# DUT1.net
KiCad netlist of a schematic drawn in Altium Designer
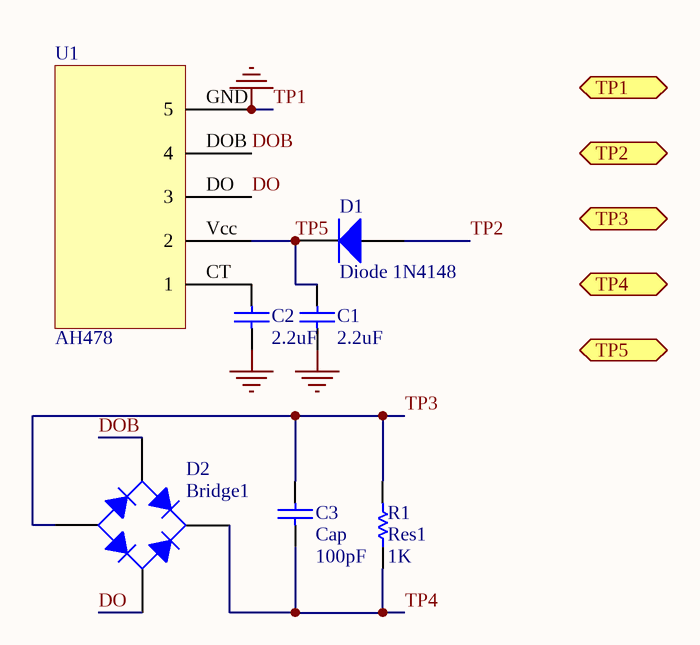
[diagram p0: DUT1.SchDoc]

(export (version "E")
  (design (tool "Eeschema 10.0.6"))
  (components
    (comp (ref "C1")
      (value "2.2uF")
      (footprint "CC1310-0504")
      (description "Capacitor (Semiconductor SIM Model)")
      (fields (field (name "Comment") "Cap Semi") (field (name "PUBLISHER") "Altium Limited"))
      (libsource (lib "Miscellaneous Devices") (part "Cap Semi"))
    )
    (comp (ref "C2")
      (value "2.2uF")
      (footprint "CC1310-0504")
      (description "Capacitor (Semiconductor SIM Model)")
      (fields (field (name "Comment") "Cap Semi") (field (name "PUBLISHER") "Altium Limited"))
      (libsource (lib "Miscellaneous Devices") (part "Cap Semi"))
    )
    (comp (ref "C3")
      (value "Cap")
      (footprint "RAD-0.3")
      (description "Capacitor")
      (fields (field (name "ALTIUM_VALUE") "100pF") (field (name "PUBLISHER") "Altium Limited"))
      (libsource (lib "Miscellaneous Devices") (part "Cap"))
    )
    (comp (ref "D1")
      (value "Diode 1N4148")
      (footprint "DIO7.1-3.9x1.9")
      (description "High Conductance Fast Diode")
      (fields (field (name "PUBLISHER") "Altium Limited"))
      (libsource (lib "Miscellaneous Devices") (part "Diode 1N4148"))
    )
    (comp (ref "D2")
      (value "Bridge1")
      (footprint "E-BIP-P4/D10")
      (description "Full Wave Diode Bridge")
      (fields (field (name "PUBLISHER") "Altium Limited"))
      (libsource (lib "Miscellaneous Devices") (part "Bridge1"))
    )
    (comp (ref "R1")
      (value "Res1")
      (footprint "AXIAL-0.3")
      (description "Resistor")
      (fields (field (name "ALTIUM_VALUE") "1K") (field (name "PUBLISHER") "Altium Limited"))
      (libsource (lib "Miscellaneous Devices") (part "Res1"))
    )
    (comp (ref "U1") (value "AH478") (libsource (lib "AH478") (part "AH478")))
  )
  (nets
    (net (code "1") (name "/DO") (class "Default")
      (node (ref "D2") (pin "4") (pinfunction "C_4") (pintype "passive"))
      (node (ref "U1") (pin "DO") (pinfunction "3_DO") (pintype "passive"))
    )
    (net (code "2") (name "/DOB") (class "Default")
      (node (ref "D2") (pin "2") (pinfunction "C_2") (pintype "passive"))
      (node (ref "U1") (pin "DOB") (pinfunction "4_DOB") (pintype "passive"))
    )
    (net (code "3") (name "/TP2") (class "Default")
      (node (ref "D1") (pin "1") (pinfunction "A_1") (pintype "passive"))
    )
    (net (code "4") (name "/TP3") (class "Default")
      (node (ref "C3") (pin "2") (pinfunction "2_2") (pintype "passive"))
      (node (ref "D2") (pin "1") (pinfunction "A_1") (pintype "passive"))
      (node (ref "R1") (pin "2") (pinfunction "2_2") (pintype "passive"))
    )
    (net (code "5") (name "/TP4") (class "Default")
      (node (ref "C3") (pin "1") (pinfunction "1_1") (pintype "passive"))
      (node (ref "D2") (pin "3") (pinfunction "K_3") (pintype "passive"))
      (node (ref "R1") (pin "1") (pinfunction "1_1") (pintype "passive"))
    )
    (net (code "6") (name "/TP5") (class "Default")
      (node (ref "C1") (pin "2") (pinfunction "2_2") (pintype "passive"))
      (node (ref "D1") (pin "2") (pinfunction "K_2") (pintype "passive"))
      (node (ref "U1") (pin "Vcc") (pinfunction "2_Vcc") (pintype "power_in"))
    )
    (net (code "7") (name "GND") (class "Default")
      (node (ref "C1") (pin "1") (pinfunction "1_1") (pintype "passive"))
      (node (ref "C2") (pin "1") (pinfunction "1_1") (pintype "passive"))
      (node (ref "U1") (pin "GND") (pinfunction "5_GND") (pintype "power_in"))
    )
    (net (code "8") (name "Net-(U1-1)") (class "Default")
      (node (ref "C2") (pin "2") (pinfunction "2_2") (pintype "passive"))
      (node (ref "U1") (pin "CT") (pinfunction "1_CT") (pintype "passive"))
    )
  )
)
